# ArmDebuger_4-7_JLink_V9.net
KiCad netlist of a schematic drawn in Altium Designer
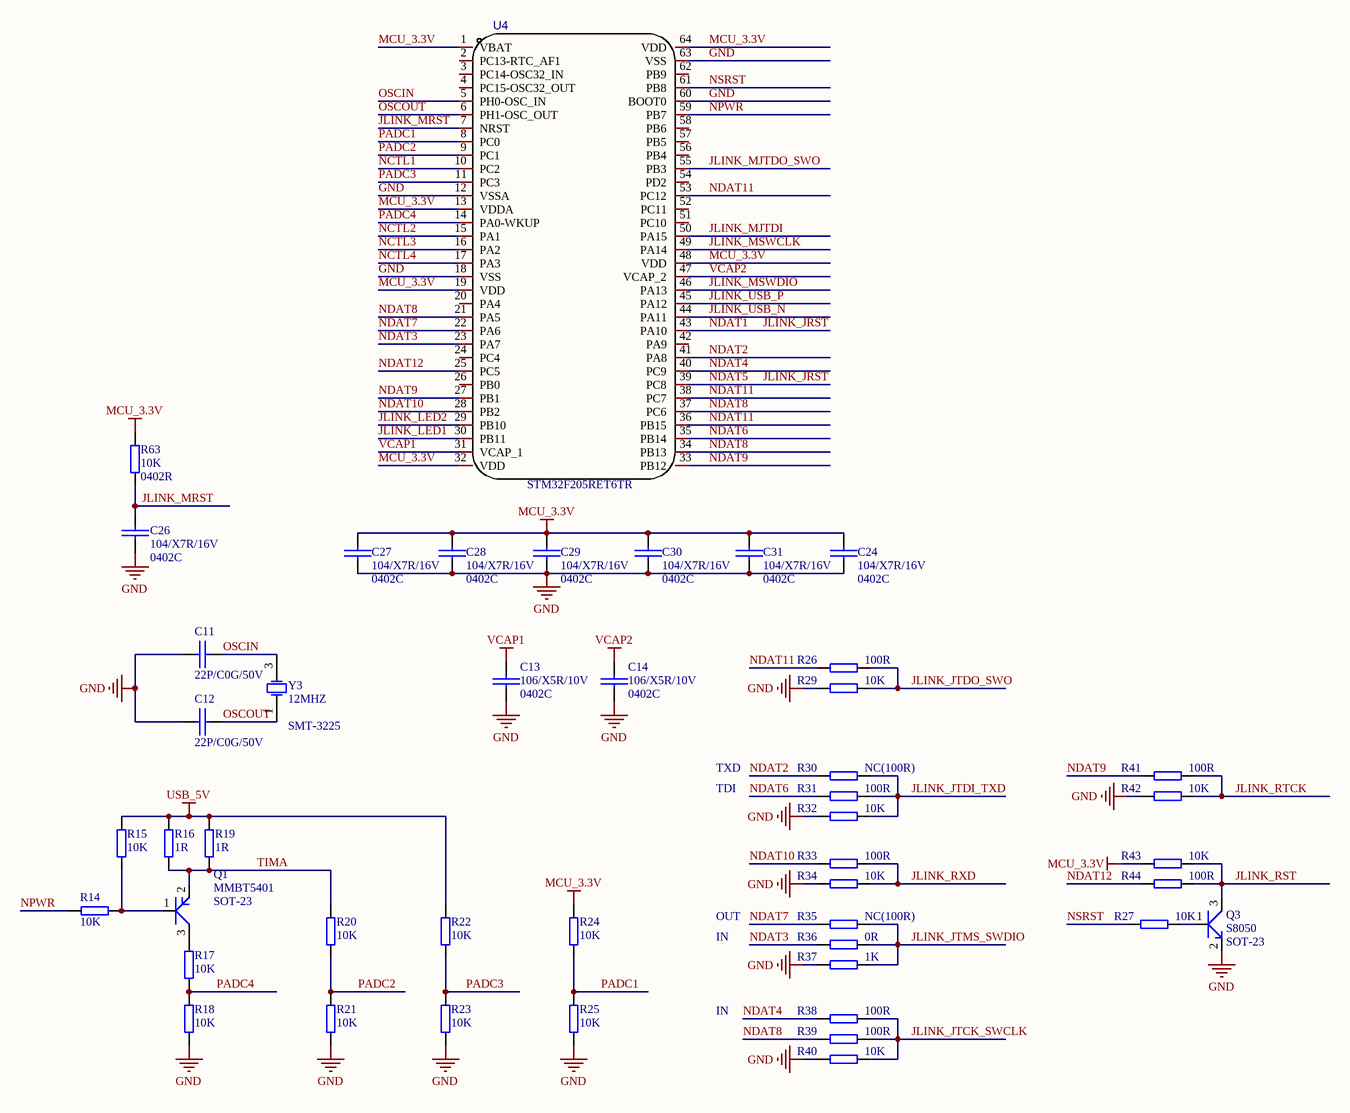
[diagram p0: ArmDebuger(4-7)JLink_V9.SchDoc]

(export (version "E")
  (design (tool "Eeschema 10.0.6"))
  (components
    (comp (ref "C11") (value "22P/C0G/50V") (footprint "0402C-SMD-M") (libsource (lib "*") (part "CAP")))
    (comp (ref "C12") (value "22P/C0G/50V") (footprint "0402C-SMD-M") (libsource (lib "*") (part "CAP")))
    (comp (ref "C13")
      (value "106/X5R/10V")
      (footprint "0402C-SMD-M")
      (fields (field (name "FP") "0402C"))
      (libsource (lib "*") (part "CAP"))
    )
    (comp (ref "C14")
      (value "106/X5R/10V")
      (footprint "0402C-SMD-M")
      (fields (field (name "FP") "0402C"))
      (libsource (lib "*") (part "CAP"))
    )
    (comp (ref "C24")
      (value "104/X7R/16V")
      (footprint "0402C-SMD-M")
      (fields (field (name "FP") "0402C"))
      (libsource (lib "*") (part "CAP"))
    )
    (comp (ref "C26")
      (value "104/X7R/16V")
      (footprint "0402C-SMD-M")
      (fields (field (name "FP") "0402C"))
      (libsource (lib "*") (part "CAP"))
    )
    (comp (ref "C27")
      (value "104/X7R/16V")
      (footprint "0402C-SMD-M")
      (fields (field (name "FP") "0402C"))
      (libsource (lib "*") (part "CAP"))
    )
    (comp (ref "C28")
      (value "104/X7R/16V")
      (footprint "0402C-SMD-M")
      (fields (field (name "FP") "0402C"))
      (libsource (lib "*") (part "CAP"))
    )
    (comp (ref "C29")
      (value "104/X7R/16V")
      (footprint "0402C-SMD-M")
      (fields (field (name "FP") "0402C"))
      (libsource (lib "*") (part "CAP"))
    )
    (comp (ref "C30")
      (value "104/X7R/16V")
      (footprint "0402C-SMD-M")
      (fields (field (name "FP") "0402C"))
      (libsource (lib "*") (part "CAP"))
    )
    (comp (ref "C31")
      (value "104/X7R/16V")
      (footprint "0402C-SMD-M")
      (fields (field (name "FP") "0402C"))
      (libsource (lib "*") (part "CAP"))
    )
    (comp (ref "Q1")
      (value "MMBT5401")
      (footprint "SOT-23")
      (fields (field (name "FP") "SOT-23"))
      (libsource (lib "sch") (part "PNP-BEC"))
    )
    (comp (ref "Q3")
      (value "S8050")
      (footprint "SOT-23")
      (fields (field (name "FP") "SOT-23"))
      (libsource (lib "sch") (part "NPN-BEC"))
    )
    (comp (ref "R14") (value "10K") (footprint "0402R-SMD-M") (libsource (lib "*") (part "RES")))
    (comp (ref "R15") (value "10K") (footprint "0402R-SMD-M") (libsource (lib "*") (part "RES")))
    (comp (ref "R16") (value "1R") (footprint "0402R-SMD-M") (libsource (lib "*") (part "RES")))
    (comp (ref "R17") (value "10K") (footprint "0402R-SMD-M") (libsource (lib "*") (part "RES")))
    (comp (ref "R18") (value "10K") (footprint "0402R-SMD-M") (libsource (lib "*") (part "RES")))
    (comp (ref "R19") (value "1R") (footprint "0402R-SMD-M") (libsource (lib "*") (part "RES")))
    (comp (ref "R20") (value "10K") (footprint "0402R-SMD-M") (libsource (lib "*") (part "RES")))
    (comp (ref "R21") (value "10K") (footprint "0402R-SMD-M") (libsource (lib "*") (part "RES")))
    (comp (ref "R22") (value "10K") (footprint "0402R-SMD-M") (libsource (lib "*") (part "RES")))
    (comp (ref "R23") (value "10K") (footprint "0402R-SMD-M") (libsource (lib "*") (part "RES")))
    (comp (ref "R24") (value "10K") (footprint "0402R-SMD-M") (libsource (lib "*") (part "RES")))
    (comp (ref "R25") (value "10K") (footprint "0402R-SMD-M") (libsource (lib "*") (part "RES")))
    (comp (ref "R26") (value "100R") (footprint "0402R-SMD-M") (libsource (lib "*") (part "RES")))
    (comp (ref "R27") (value "10K") (footprint "0402R-SMD-M") (libsource (lib "*") (part "RES")))
    (comp (ref "R29") (value "10K") (footprint "0402R-SMD-M") (libsource (lib "*") (part "RES")))
    (comp (ref "R30") (value "NC(100R)") (footprint "0402R-SMD-M") (libsource (lib "*") (part "RES")))
    (comp (ref "R31") (value "100R") (footprint "0402R-SMD-M") (libsource (lib "*") (part "RES")))
    (comp (ref "R32") (value "10K") (footprint "0402R-SMD-M") (libsource (lib "*") (part "RES")))
    (comp (ref "R33") (value "100R") (footprint "0402R-SMD-M") (libsource (lib "*") (part "RES")))
    (comp (ref "R34") (value "10K") (footprint "0402R-SMD-M") (libsource (lib "*") (part "RES")))
    (comp (ref "R35") (value "NC(100R)") (footprint "0402R-SMD-M") (libsource (lib "*") (part "RES")))
    (comp (ref "R36") (value "0R") (footprint "0402R-SMD-M") (libsource (lib "*") (part "RES")))
    (comp (ref "R37") (value "1K") (footprint "0402R-SMD-M") (libsource (lib "*") (part "RES")))
    (comp (ref "R38") (value "100R") (footprint "0402R-SMD-M") (libsource (lib "*") (part "RES")))
    (comp (ref "R39") (value "100R") (footprint "0402R-SMD-M") (libsource (lib "*") (part "RES")))
    (comp (ref "R40") (value "10K") (footprint "0402R-SMD-M") (libsource (lib "*") (part "RES")))
    (comp (ref "R41") (value "100R") (footprint "0402R-SMD-M") (libsource (lib "*") (part "RES")))
    (comp (ref "R42") (value "10K") (footprint "0402R-SMD-M") (libsource (lib "*") (part "RES")))
    (comp (ref "R43") (value "10K") (footprint "0402R-SMD-M") (libsource (lib "*") (part "RES")))
    (comp (ref "R44") (value "100R") (footprint "0402R-SMD-M") (libsource (lib "*") (part "RES")))
    (comp (ref "R63")
      (value "10K")
      (footprint "0402R-SMD-M")
      (fields (field (name "FP") "0402R"))
      (libsource (lib "*") (part "RES"))
    )
    (comp (ref "U4")
      (value "STM32F205RET6TR")
      (footprint "LQFP64_L")
      (libsource (lib "altium-import") (part "root_0_STM32F205RET6TR_"))
    )
    (comp (ref "Y3")
      (value "12MHZ")
      (footprint "CRYSTAL-SMT-3225")
      (description "贴片晶振")
      (fields (field (name "FP") "SMT-3225"))
      (libsource (lib "CrystalOscillator") (part "SMD-3225_4P  25MHZ 12PF 10PPM"))
    )
  )
  (nets
    (net (code "1") (name "/JLINK_JRST") (class "Default")
      (node (ref "U4") (pin "39") (pinfunction "PC8_39") (pintype "passive"))
      (node (ref "U4") (pin "43") (pinfunction "PA10_43") (pintype "passive"))
    )
    (net (code "2") (name "/JLINK_JTCK_SWCLK") (class "Default")
      (node (ref "R38") (pin "2") (pinfunction "2_2") (pintype "passive"))
      (node (ref "R39") (pin "2") (pinfunction "2_2") (pintype "passive"))
      (node (ref "R40") (pin "2") (pinfunction "2_2") (pintype "passive"))
    )
    (net (code "3") (name "/JLINK_JTDI_TXD") (class "Default")
      (node (ref "R30") (pin "2") (pinfunction "2_2") (pintype "passive"))
      (node (ref "R31") (pin "2") (pinfunction "2_2") (pintype "passive"))
      (node (ref "R32") (pin "2") (pinfunction "2_2") (pintype "passive"))
    )
    (net (code "4") (name "/JLINK_JTDO_SWO") (class "Default")
      (node (ref "R26") (pin "2") (pinfunction "2_2") (pintype "passive"))
      (node (ref "R29") (pin "2") (pinfunction "2_2") (pintype "passive"))
    )
    (net (code "5") (name "/JLINK_JTMS_SWDIO") (class "Default")
      (node (ref "R35") (pin "2") (pinfunction "2_2") (pintype "passive"))
      (node (ref "R36") (pin "2") (pinfunction "2_2") (pintype "passive"))
      (node (ref "R37") (pin "2") (pinfunction "2_2") (pintype "passive"))
    )
    (net (code "6") (name "/JLINK_LED1") (class "Default")
      (node (ref "U4") (pin "30") (pinfunction "PB11_30") (pintype "passive"))
    )
    (net (code "7") (name "/JLINK_LED2") (class "Default")
      (node (ref "U4") (pin "29") (pinfunction "PB10_29") (pintype "passive"))
    )
    (net (code "8") (name "/JLINK_MJTDI") (class "Default")
      (node (ref "U4") (pin "50") (pinfunction "PA15_50") (pintype "passive"))
    )
    (net (code "9") (name "/JLINK_MJTDO_SWO") (class "Default")
      (node (ref "U4") (pin "55") (pinfunction "PB3_55") (pintype "passive"))
    )
    (net (code "10") (name "/JLINK_MRST") (class "Default")
      (node (ref "C26") (pin "2") (pinfunction "1_2") (pintype "passive"))
      (node (ref "R63") (pin "2") (pinfunction "2_2") (pintype "passive"))
      (node (ref "U4") (pin "7") (pinfunction "NRST_7") (pintype "passive"))
    )
    (net (code "11") (name "/JLINK_MSWCLK") (class "Default")
      (node (ref "U4") (pin "49") (pinfunction "PA14_49") (pintype "passive"))
    )
    (net (code "12") (name "/JLINK_MSWDIO") (class "Default")
      (node (ref "U4") (pin "46") (pinfunction "PA13_46") (pintype "passive"))
    )
    (net (code "13") (name "/JLINK_RST") (class "Default")
      (node (ref "Q3") (pin "3") (pinfunction "C_3") (pintype "passive"))
      (node (ref "R43") (pin "2") (pinfunction "2_2") (pintype "passive"))
      (node (ref "R44") (pin "2") (pinfunction "2_2") (pintype "passive"))
    )
    (net (code "14") (name "/JLINK_RTCK") (class "Default")
      (node (ref "R41") (pin "2") (pinfunction "2_2") (pintype "passive"))
      (node (ref "R42") (pin "2") (pinfunction "2_2") (pintype "passive"))
    )
    (net (code "15") (name "/JLINK_RXD") (class "Default")
      (node (ref "R33") (pin "2") (pinfunction "2_2") (pintype "passive"))
      (node (ref "R34") (pin "2") (pinfunction "2_2") (pintype "passive"))
    )
    (net (code "16") (name "/JLINK_USB_N") (class "Default")
      (node (ref "U4") (pin "44") (pinfunction "PA11_44") (pintype "passive"))
    )
    (net (code "17") (name "/JLINK_USB_P") (class "Default")
      (node (ref "U4") (pin "45") (pinfunction "PA12_45") (pintype "passive"))
    )
    (net (code "18") (name "/NCTL1") (class "Default")
      (node (ref "U4") (pin "10") (pinfunction "PC2_10") (pintype "passive"))
    )
    (net (code "19") (name "/NCTL2") (class "Default")
      (node (ref "U4") (pin "15") (pinfunction "PA1_15") (pintype "passive"))
    )
    (net (code "20") (name "/NCTL3") (class "Default")
      (node (ref "U4") (pin "16") (pinfunction "PA2_16") (pintype "passive"))
    )
    (net (code "21") (name "/NCTL4") (class "Default")
      (node (ref "U4") (pin "17") (pinfunction "PA3_17") (pintype "passive"))
    )
    (net (code "22") (name "/NDAT2") (class "Default")
      (node (ref "R30") (pin "1") (pinfunction "1_1") (pintype "passive"))
      (node (ref "U4") (pin "41") (pinfunction "PA8_41") (pintype "passive"))
    )
    (net (code "23") (name "/NDAT3") (class "Default")
      (node (ref "R36") (pin "1") (pinfunction "1_1") (pintype "passive"))
      (node (ref "U4") (pin "23") (pinfunction "PA7_23") (pintype "passive"))
    )
    (net (code "24") (name "/NDAT4") (class "Default")
      (node (ref "R38") (pin "1") (pinfunction "1_1") (pintype "passive"))
      (node (ref "U4") (pin "40") (pinfunction "PC9_40") (pintype "passive"))
    )
    (net (code "25") (name "/NDAT6") (class "Default")
      (node (ref "R31") (pin "1") (pinfunction "1_1") (pintype "passive"))
      (node (ref "U4") (pin "35") (pinfunction "PB14_35") (pintype "passive"))
    )
    (net (code "26") (name "/NDAT7") (class "Default")
      (node (ref "R35") (pin "1") (pinfunction "1_1") (pintype "passive"))
      (node (ref "U4") (pin "22") (pinfunction "PA6_22") (pintype "passive"))
    )
    (net (code "27") (name "/NDAT8") (class "Default")
      (node (ref "R39") (pin "1") (pinfunction "1_1") (pintype "passive"))
      (node (ref "U4") (pin "21") (pinfunction "PA5_21") (pintype "passive"))
      (node (ref "U4") (pin "34") (pinfunction "PB13_34") (pintype "passive"))
      (node (ref "U4") (pin "37") (pinfunction "PC6_37") (pintype "passive"))
    )
    (net (code "28") (name "/NDAT9") (class "Default")
      (node (ref "R41") (pin "1") (pinfunction "1_1") (pintype "passive"))
      (node (ref "U4") (pin "27") (pinfunction "PB1_27") (pintype "passive"))
      (node (ref "U4") (pin "33") (pinfunction "PB12_33") (pintype "passive"))
    )
    (net (code "29") (name "/NDAT10") (class "Default")
      (node (ref "R33") (pin "1") (pinfunction "1_1") (pintype "passive"))
      (node (ref "U4") (pin "28") (pinfunction "PB2_28") (pintype "passive"))
    )
    (net (code "30") (name "/NDAT11") (class "Default")
      (node (ref "R26") (pin "1") (pinfunction "1_1") (pintype "passive"))
      (node (ref "U4") (pin "36") (pinfunction "PB15_36") (pintype "passive"))
      (node (ref "U4") (pin "38") (pinfunction "PC7_38") (pintype "passive"))
      (node (ref "U4") (pin "53") (pinfunction "PC12_53") (pintype "passive"))
    )
    (net (code "31") (name "/NDAT12") (class "Default")
      (node (ref "R44") (pin "1") (pinfunction "1_1") (pintype "passive"))
      (node (ref "U4") (pin "25") (pinfunction "PC5_25") (pintype "passive"))
    )
    (net (code "32") (name "/NPWR") (class "Default")
      (node (ref "R14") (pin "2") (pinfunction "2_2") (pintype "passive"))
      (node (ref "U4") (pin "59") (pinfunction "PB7_59") (pintype "passive"))
    )
    (net (code "33") (name "/NSRST") (class "Default")
      (node (ref "R27") (pin "1") (pinfunction "1_1") (pintype "passive"))
      (node (ref "U4") (pin "61") (pinfunction "PB8_61") (pintype "passive"))
    )
    (net (code "34") (name "/OSCIN") (class "Default")
      (node (ref "C11") (pin "2") (pinfunction "1_2") (pintype "passive"))
      (node (ref "U4") (pin "5") (pinfunction "PH0-OSC_IN_5") (pintype "passive"))
      (node (ref "Y3") (pin "3") (pinfunction "OSC2_3") (pintype "passive"))
    )
    (net (code "35") (name "/OSCOUT") (class "Default")
      (node (ref "C12") (pin "2") (pinfunction "1_2") (pintype "passive"))
      (node (ref "U4") (pin "6") (pinfunction "PH1-OSC_OUT_6") (pintype "passive"))
      (node (ref "Y3") (pin "1") (pinfunction "OSC1_1") (pintype "passive"))
    )
    (net (code "36") (name "/PADC1") (class "Default")
      (node (ref "R24") (pin "2") (pinfunction "2_2") (pintype "passive"))
      (node (ref "R25") (pin "1") (pinfunction "1_1") (pintype "passive"))
      (node (ref "U4") (pin "8") (pinfunction "PC0_8") (pintype "passive"))
    )
    (net (code "37") (name "/PADC2") (class "Default")
      (node (ref "R20") (pin "2") (pinfunction "2_2") (pintype "passive"))
      (node (ref "R21") (pin "1") (pinfunction "1_1") (pintype "passive"))
      (node (ref "U4") (pin "9") (pinfunction "PC1_9") (pintype "passive"))
    )
    (net (code "38") (name "/PADC3") (class "Default")
      (node (ref "R22") (pin "2") (pinfunction "2_2") (pintype "passive"))
      (node (ref "R23") (pin "1") (pinfunction "1_1") (pintype "passive"))
      (node (ref "U4") (pin "11") (pinfunction "PC3_11") (pintype "passive"))
    )
    (net (code "39") (name "/PADC4") (class "Default")
      (node (ref "R17") (pin "2") (pinfunction "2_2") (pintype "passive"))
      (node (ref "R18") (pin "1") (pinfunction "1_1") (pintype "passive"))
      (node (ref "U4") (pin "14") (pinfunction "PA0-WKUP_14") (pintype "passive"))
    )
    (net (code "40") (name "/TIMA") (class "Default")
      (node (ref "Q1") (pin "2") (pinfunction "E_2") (pintype "passive"))
      (node (ref "R16") (pin "2") (pinfunction "2_2") (pintype "passive"))
      (node (ref "R19") (pin "2") (pinfunction "2_2") (pintype "passive"))
      (node (ref "R20") (pin "1") (pinfunction "1_1") (pintype "passive"))
    )
    (net (code "41") (name "GND") (class "Default")
      (node (ref "C11") (pin "1") (pinfunction "1_1") (pintype "passive"))
      (node (ref "C12") (pin "1") (pinfunction "1_1") (pintype "passive"))
      (node (ref "C13") (pin "2") (pinfunction "1_2") (pintype "passive"))
      (node (ref "C14") (pin "2") (pinfunction "1_2") (pintype "passive"))
      (node (ref "C24") (pin "1") (pinfunction "1_1") (pintype "passive"))
      (node (ref "C26") (pin "1") (pinfunction "1_1") (pintype "passive"))
      (node (ref "C27") (pin "1") (pinfunction "1_1") (pintype "passive"))
      (node (ref "C28") (pin "1") (pinfunction "1_1") (pintype "passive"))
      (node (ref "C29") (pin "1") (pinfunction "1_1") (pintype "passive"))
      (node (ref "C30") (pin "1") (pinfunction "1_1") (pintype "passive"))
      (node (ref "C31") (pin "1") (pinfunction "1_1") (pintype "passive"))
      (node (ref "Q3") (pin "2") (pinfunction "E_2") (pintype "passive"))
      (node (ref "R18") (pin "2") (pinfunction "2_2") (pintype "passive"))
      (node (ref "R21") (pin "2") (pinfunction "2_2") (pintype "passive"))
      (node (ref "R23") (pin "2") (pinfunction "2_2") (pintype "passive"))
      (node (ref "R25") (pin "2") (pinfunction "2_2") (pintype "passive"))
      (node (ref "R29") (pin "1") (pinfunction "1_1") (pintype "passive"))
      (node (ref "R32") (pin "1") (pinfunction "1_1") (pintype "passive"))
      (node (ref "R34") (pin "1") (pinfunction "1_1") (pintype "passive"))
      (node (ref "R37") (pin "1") (pinfunction "1_1") (pintype "passive"))
      (node (ref "R40") (pin "1") (pinfunction "1_1") (pintype "passive"))
      (node (ref "R42") (pin "1") (pinfunction "1_1") (pintype "passive"))
      (node (ref "U4") (pin "12") (pinfunction "VSSA_12") (pintype "passive"))
      (node (ref "U4") (pin "18") (pinfunction "VSS_18") (pintype "passive"))
      (node (ref "U4") (pin "60") (pinfunction "BOOT0_60") (pintype "passive"))
      (node (ref "U4") (pin "63") (pinfunction "VSS_63") (pintype "passive"))
    )
    (net (code "42") (name "MCU_3.3V") (class "Default")
      (node (ref "C24") (pin "2") (pinfunction "1_2") (pintype "passive"))
      (node (ref "C27") (pin "2") (pinfunction "1_2") (pintype "passive"))
      (node (ref "C28") (pin "2") (pinfunction "1_2") (pintype "passive"))
      (node (ref "C29") (pin "2") (pinfunction "1_2") (pintype "passive"))
      (node (ref "C30") (pin "2") (pinfunction "1_2") (pintype "passive"))
      (node (ref "C31") (pin "2") (pinfunction "1_2") (pintype "passive"))
      (node (ref "R24") (pin "1") (pinfunction "1_1") (pintype "passive"))
      (node (ref "R43") (pin "1") (pinfunction "1_1") (pintype "passive"))
      (node (ref "R63") (pin "1") (pinfunction "1_1") (pintype "passive"))
      (node (ref "U4") (pin "1") (pinfunction "VBAT_1") (pintype "passive"))
      (node (ref "U4") (pin "13") (pinfunction "VDDA_13") (pintype "passive"))
      (node (ref "U4") (pin "19") (pinfunction "VDD_19") (pintype "passive"))
      (node (ref "U4") (pin "32") (pinfunction "VDD_32") (pintype "passive"))
      (node (ref "U4") (pin "48") (pinfunction "VDD_48") (pintype "passive"))
      (node (ref "U4") (pin "64") (pinfunction "VDD_64") (pintype "passive"))
    )
    (net (code "43") (name "Net-(Q1-B)") (class "Default")
      (node (ref "Q1") (pin "1") (pinfunction "B_1") (pintype "passive"))
      (node (ref "R14") (pin "1") (pinfunction "1_1") (pintype "passive"))
      (node (ref "R15") (pin "1") (pinfunction "1_1") (pintype "passive"))
    )
    (net (code "44") (name "Net-(Q1-C)") (class "Default")
      (node (ref "Q1") (pin "3") (pinfunction "C_3") (pintype "passive"))
      (node (ref "R17") (pin "1") (pinfunction "1_1") (pintype "passive"))
    )
    (net (code "45") (name "Net-(Q3-B)") (class "Default")
      (node (ref "Q3") (pin "1") (pinfunction "B_1") (pintype "passive"))
      (node (ref "R27") (pin "2") (pinfunction "2_2") (pintype "passive"))
    )
    (net (code "46") (name "USB_5V") (class "Default")
      (node (ref "R15") (pin "2") (pinfunction "2_2") (pintype "passive"))
      (node (ref "R16") (pin "1") (pinfunction "1_1") (pintype "passive"))
      (node (ref "R19") (pin "1") (pinfunction "1_1") (pintype "passive"))
      (node (ref "R22") (pin "1") (pinfunction "1_1") (pintype "passive"))
    )
    (net (code "47") (name "VCAP1") (class "Default")
      (node (ref "C13") (pin "1") (pinfunction "1_1") (pintype "passive"))
      (node (ref "U4") (pin "31") (pinfunction "VCAP_1_31") (pintype "passive"))
    )
    (net (code "48") (name "VCAP2") (class "Default")
      (node (ref "C14") (pin "1") (pinfunction "1_1") (pintype "passive"))
      (node (ref "U4") (pin "47") (pinfunction "VCAP_2_47") (pintype "passive"))
    )
    (net (code "49") (name "unconnected-(U4-PA4-Pad20)") (class "Default")
      (node (ref "U4") (pin "20") (pinfunction "PA4_20") (pintype "passive"))
    )
    (net (code "50") (name "unconnected-(U4-PA9-Pad42)") (class "Default")
      (node (ref "U4") (pin "42") (pinfunction "PA9_42") (pintype "passive"))
    )
    (net (code "51") (name "unconnected-(U4-PB0-Pad26)") (class "Default")
      (node (ref "U4") (pin "26") (pinfunction "PB0_26") (pintype "passive"))
    )
    (net (code "52") (name "unconnected-(U4-PB4-Pad56)") (class "Default")
      (node (ref "U4") (pin "56") (pinfunction "PB4_56") (pintype "passive"))
    )
    (net (code "53") (name "unconnected-(U4-PB5-Pad57)") (class "Default")
      (node (ref "U4") (pin "57") (pinfunction "PB5_57") (pintype "passive"))
    )
    (net (code "54") (name "unconnected-(U4-PB6-Pad58)") (class "Default")
      (node (ref "U4") (pin "58") (pinfunction "PB6_58") (pintype "passive"))
    )
    (net (code "55") (name "unconnected-(U4-PB9-Pad62)") (class "Default")
      (node (ref "U4") (pin "62") (pinfunction "PB9_62") (pintype "passive"))
    )
    (net (code "56") (name "unconnected-(U4-PC4-Pad24)") (class "Default")
      (node (ref "U4") (pin "24") (pinfunction "PC4_24") (pintype "passive"))
    )
    (net (code "57") (name "unconnected-(U4-PC10-Pad51)") (class "Default")
      (node (ref "U4") (pin "51") (pinfunction "PC10_51") (pintype "passive"))
    )
    (net (code "58") (name "unconnected-(U4-PC11-Pad52)") (class "Default")
      (node (ref "U4") (pin "52") (pinfunction "PC11_52") (pintype "passive"))
    )
    (net (code "59") (name "unconnected-(U4-PC13-RTC_AF1-Pad2)") (class "Default")
      (node (ref "U4") (pin "2") (pinfunction "PC13-RTC_AF1_2") (pintype "passive"))
    )
    (net (code "60") (name "unconnected-(U4-PC14-OSC32_IN-Pad3)") (class "Default")
      (node (ref "U4") (pin "3") (pinfunction "PC14-OSC32_IN_3") (pintype "passive"))
    )
    (net (code "61") (name "unconnected-(U4-PC15-OSC32_OUT-Pad4)") (class "Default")
      (node (ref "U4") (pin "4") (pinfunction "PC15-OSC32_OUT_4") (pintype "passive"))
    )
    (net (code "62") (name "unconnected-(U4-PD2-Pad54)") (class "Default")
      (node (ref "U4") (pin "54") (pinfunction "PD2_54") (pintype "passive"))
    )
  )
)
